# Nixie_clock.net
KiCad netlist of a schematic drawn in EAGLE
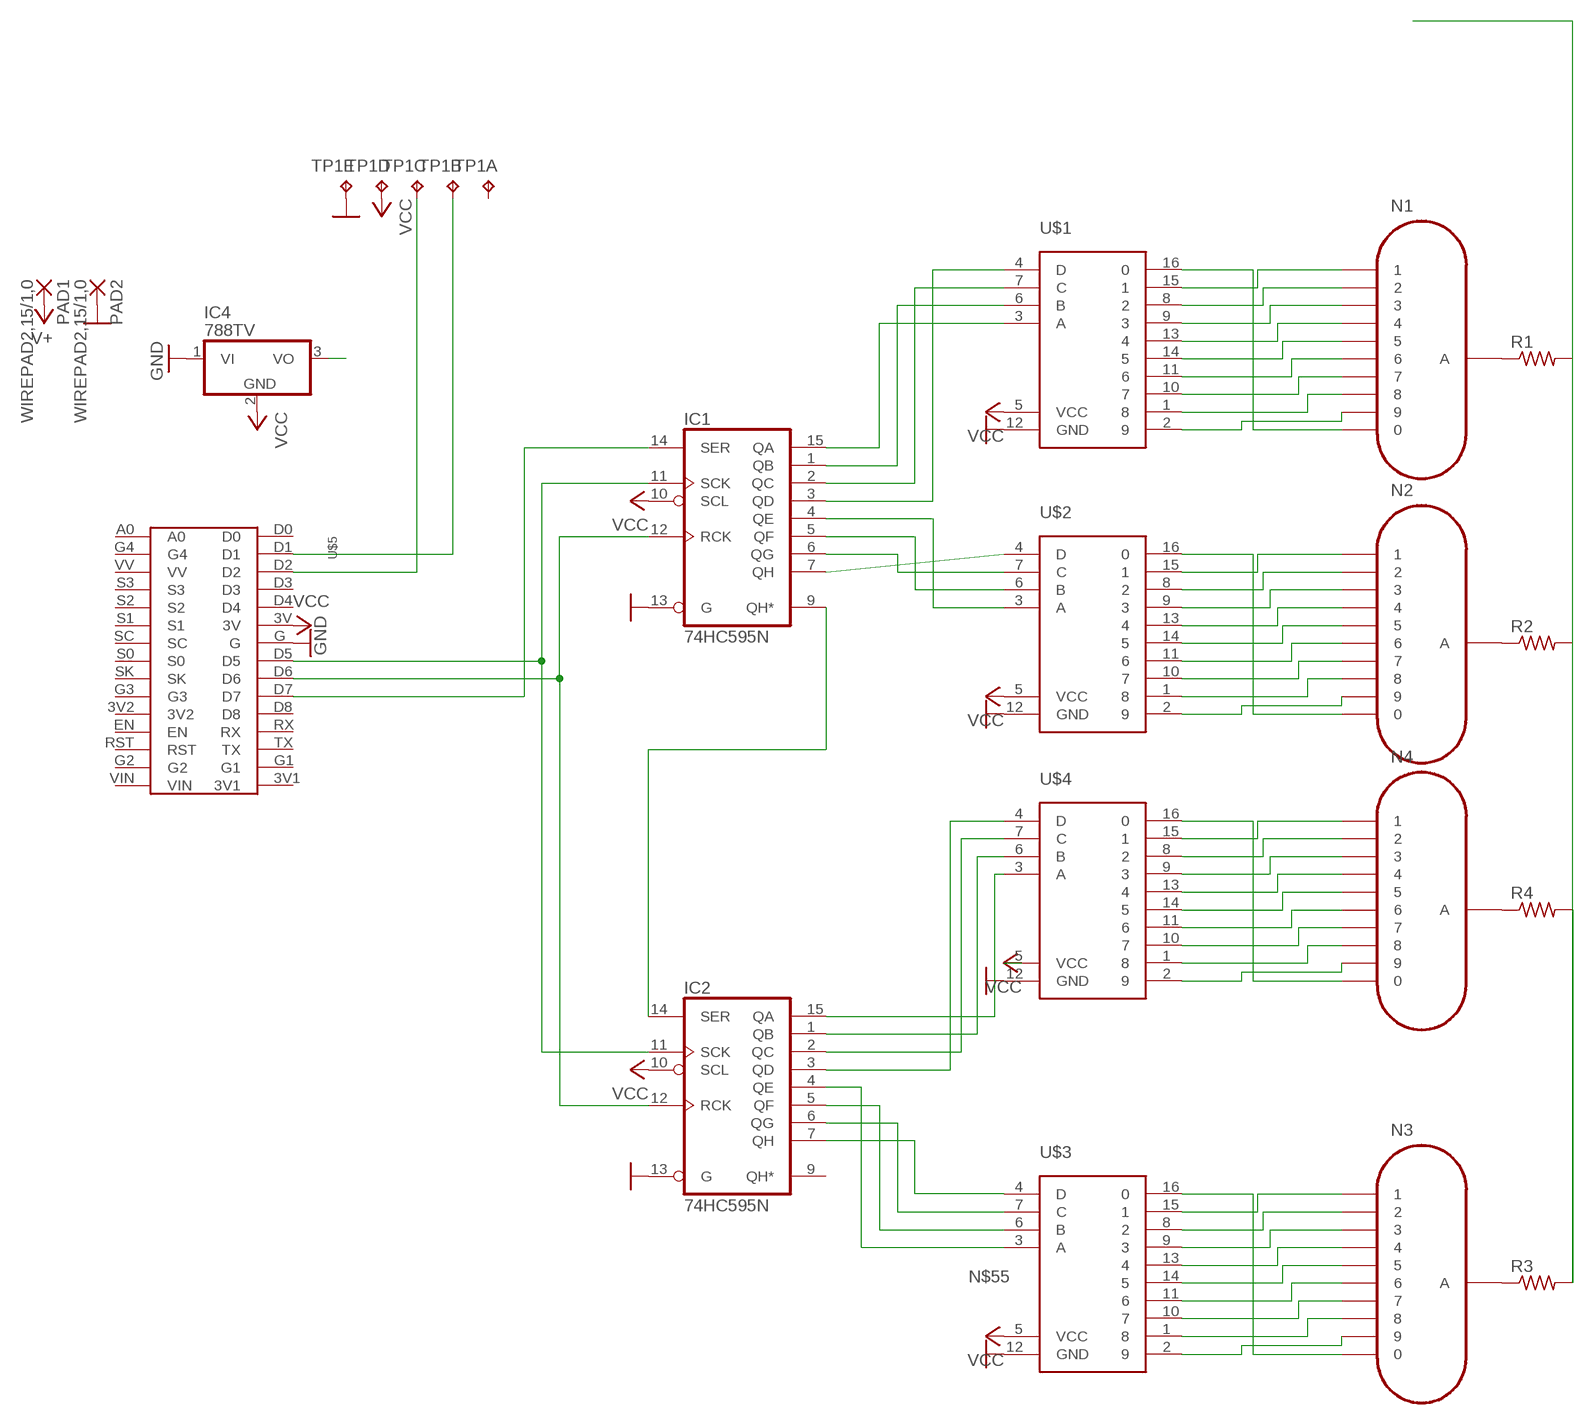
[diagram p0: schematic, sheet 1]
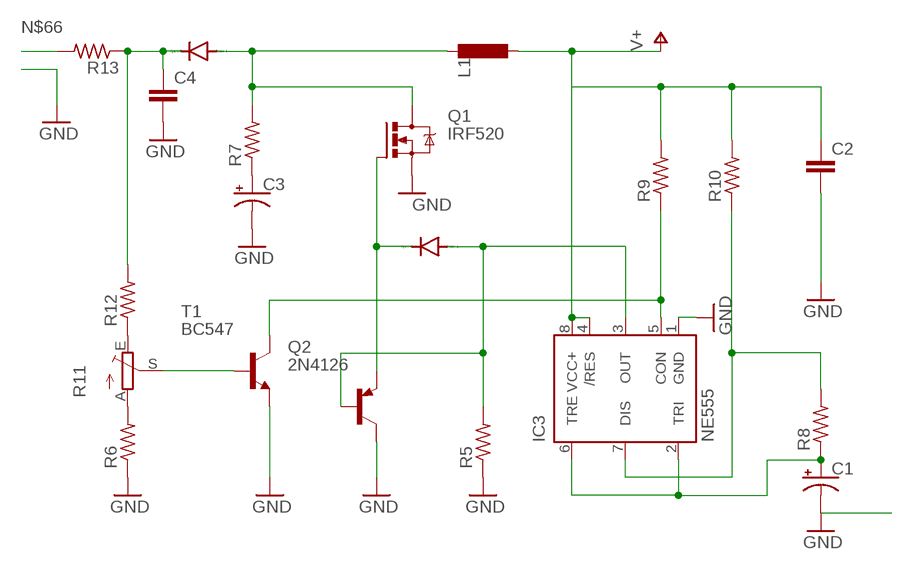
[diagram p1: schematic, sheet 2]

(export (version "E")
  (design (tool "Eeschema 10.0.6"))
  (components
    (comp (ref "C1")
      (value "CPOL-USTAP5-80")
      (footprint "eagle-import:TAP5-80")
      (libsource (lib "eagle-import") (part "CPOL-USTAP5-80"))
    )
    (comp (ref "C2")
      (value "C-EU025-025X050")
      (footprint "eagle-import:C025-025X050")
      (libsource (lib "eagle-import") (part "C-EU025-025X050"))
    )
    (comp (ref "C3")
      (value "CPOL-USTAP5-80")
      (footprint "eagle-import:TAP5-80")
      (libsource (lib "eagle-import") (part "CPOL-USTAP5-80"))
    )
    (comp (ref "C4")
      (value "C-EU025-025X050")
      (footprint "eagle-import:C025-025X050")
      (libsource (lib "eagle-import") (part "C-EU025-025X050"))
    )
    (comp (ref "D1")
      (value "1N4004")
      (footprint "eagle-import:DO41-10")
      (libsource (lib "eagle-import") (part "1N4004"))
    )
    (comp (ref "D2")
      (value "1N4004")
      (footprint "eagle-import:DO41-10")
      (libsource (lib "eagle-import") (part "1N4004"))
    )
    (comp (ref "IC3")
      (value "NE555")
      (footprint "eagle-import:DIL-08")
      (fields (field (name "MF") "Arrow Electronics") (field (name "MPN") "NE555N"))
      (libsource (lib "eagle-import") (part "NE555"))
    )
    (comp (ref "L1")
      (value "L-EU0204V")
      (footprint "eagle-import:0204V")
      (libsource (lib "eagle-import") (part "L-EU0204V"))
    )
    (comp (ref "Q1")
      (value "IRF520")
      (footprint "eagle-import:TO220BV")
      (libsource (lib "eagle-import") (part "IRF520"))
    )
    (comp (ref "Q2")
      (value "2N4126")
      (footprint "eagle-import:TO92-CBE")
      (libsource (lib "eagle-import") (part "2N4126"))
    )
    (comp (ref "R5")
      (value "R-US_0204/7")
      (footprint "eagle-import:0204_7")
      (libsource (lib "eagle-import") (part "rcl_334_R-US_0204/7"))
    )
    (comp (ref "R6")
      (value "R-US_0204/7")
      (footprint "eagle-import:0204_7")
      (libsource (lib "eagle-import") (part "rcl_334_R-US_0204/7"))
    )
    (comp (ref "R7")
      (value "R-US_0204/7")
      (footprint "eagle-import:0204_7")
      (libsource (lib "eagle-import") (part "rcl_334_R-US_0204/7"))
    )
    (comp (ref "R8")
      (value "R-US_0204/7")
      (footprint "eagle-import:0204_7")
      (libsource (lib "eagle-import") (part "rcl_334_R-US_0204/7"))
    )
    (comp (ref "R9")
      (value "R-US_0204/7")
      (footprint "eagle-import:0204_7")
      (libsource (lib "eagle-import") (part "rcl_334_R-US_0204/7"))
    )
    (comp (ref "R10")
      (value "R-US_0204/7")
      (footprint "eagle-import:0204_7")
      (libsource (lib "eagle-import") (part "rcl_334_R-US_0204/7"))
    )
    (comp (ref "R11")
      (value "TRIM_EU-S75H")
      (footprint "eagle-import:S75H")
      (libsource (lib "eagle-import") (part "TRIM_EU-S75H"))
    )
    (comp (ref "R12")
      (value "R-US_0204/7")
      (footprint "eagle-import:0204_7")
      (libsource (lib "eagle-import") (part "rcl_334_R-US_0204/7"))
    )
    (comp (ref "R13")
      (value "R-US_0204/7")
      (footprint "eagle-import:0204_7")
      (libsource (lib "eagle-import") (part "rcl_334_R-US_0204/7"))
    )
    (comp (ref "T1")
      (value "BC547")
      (footprint "eagle-import:TO92")
      (libsource (lib "eagle-import") (part "BC547"))
    )
    (comp (ref "IC1")
      (value "74HC595N")
      (footprint "eagle-import:DIL16")
      (libsource (lib "eagle-import") (part "74595NHC"))
    )
    (comp (ref "IC2")
      (value "74HC595N")
      (footprint "eagle-import:DIL16")
      (libsource (lib "eagle-import") (part "74595NHC"))
    )
    (comp (ref "IC4")
      (value "788TV")
      (footprint "eagle-import:TO220V")
      (libsource (lib "eagle-import") (part "78TV8"))
    )
    (comp (ref "N1")
      (value "IN-12A")
      (footprint "eagle-import:IN-12")
      (libsource (lib "eagle-import") (part "IN-12A"))
    )
    (comp (ref "N2")
      (value "IN-12A")
      (footprint "eagle-import:IN-12")
      (libsource (lib "eagle-import") (part "IN-12A"))
    )
    (comp (ref "N3")
      (value "IN-12A")
      (footprint "eagle-import:IN-12")
      (libsource (lib "eagle-import") (part "IN-12A"))
    )
    (comp (ref "N4")
      (value "IN-12A")
      (footprint "eagle-import:IN-12")
      (libsource (lib "eagle-import") (part "IN-12A"))
    )
    (comp (ref "PAD1")
      (value "WIREPAD2,15/1,0")
      (footprint "eagle-import:2,15_1,0")
      (libsource (lib "eagle-import") (part "WIREPAD2,15/1,0"))
    )
    (comp (ref "PAD2")
      (value "WIREPAD2,15/1,0")
      (footprint "eagle-import:2,15_1,0")
      (libsource (lib "eagle-import") (part "WIREPAD2,15/1,0"))
    )
    (comp (ref "R1")
      (value "R-US_0207/10")
      (footprint "eagle-import:0207_10")
      (libsource (lib "eagle-import") (part "R-US_0207/10"))
    )
    (comp (ref "R2")
      (value "R-US_0207/10")
      (footprint "eagle-import:0207_10")
      (libsource (lib "eagle-import") (part "R-US_0207/10"))
    )
    (comp (ref "R3")
      (value "R-US_0207/10")
      (footprint "eagle-import:0207_10")
      (libsource (lib "eagle-import") (part "R-US_0207/10"))
    )
    (comp (ref "R4")
      (value "R-US_0207/10")
      (footprint "eagle-import:0207_10")
      (libsource (lib "eagle-import") (part "R-US_0207/10"))
    )
    (comp (ref "TP1")
      (value "TP5P5-25-13")
      (footprint "eagle-import:P5-25-13")
      (libsource (lib "eagle-import") (part "TP5P5-25-13"))
    )
    (comp (ref "U$1")
      (value "K155ID1")
      (footprint "eagle-import:DIL16-KIT")
      (libsource (lib "eagle-import") (part "K155ID1"))
    )
    (comp (ref "U$2")
      (value "K155ID1")
      (footprint "eagle-import:DIL16-KIT")
      (libsource (lib "eagle-import") (part "K155ID1"))
    )
    (comp (ref "U$3")
      (value "K155ID1")
      (footprint "eagle-import:DIL16-KIT")
      (libsource (lib "eagle-import") (part "K155ID1"))
    )
    (comp (ref "U$4")
      (value "K155ID1")
      (footprint "eagle-import:DIL16-KIT")
      (libsource (lib "eagle-import") (part "K155ID1"))
    )
    (comp (ref "U$5")
      (value "LOLIN")
      (footprint "eagle-import:LOLIN")
      (libsource (lib "eagle-import") (part "LOLIN"))
    )
  )
  (nets
    (net (code "1") (name "GND") (class "Default")
      (node (ref "C1") (pin "-") (pinfunction "-_-") (pintype "passive"))
      (node (ref "C2") (pin "2") (pinfunction "2_2") (pintype "passive"))
      (node (ref "C3") (pin "-") (pinfunction "-_-") (pintype "passive"))
      (node (ref "C4") (pin "2") (pinfunction "2_2") (pintype "passive"))
      (node (ref "IC1") (pin "13") (pinfunction "G_13") (pintype "input"))
      (node (ref "IC2") (pin "13") (pinfunction "G_13") (pintype "input"))
      (node (ref "IC3") (pin "1") (pinfunction "GND_1") (pintype "power_in"))
      (node (ref "IC4") (pin "1") (pinfunction "VI_1") (pintype "input"))
      (node (ref "PAD2") (pin "1") (pinfunction "P_1") (pintype "passive"))
      (node (ref "Q1") (pin "S") (pinfunction "S_S") (pintype "passive"))
      (node (ref "Q2") (pin "C") (pinfunction "C_C") (pintype "passive"))
      (node (ref "R5") (pin "1") (pinfunction "1_1") (pintype "passive"))
      (node (ref "R6") (pin "1") (pinfunction "1_1") (pintype "passive"))
      (node (ref "T1") (pin "1") (pinfunction "E_1") (pintype "passive"))
      (node (ref "TP1") (pin "TP-5") (pinfunction "TP_TP-5") (pintype "input"))
      (node (ref "U$1") (pin "12") (pinfunction "GND_12") (pintype "bidirectional"))
      (node (ref "U$2") (pin "12") (pinfunction "GND_12") (pintype "bidirectional"))
      (node (ref "U$3") (pin "12") (pinfunction "GND_12") (pintype "bidirectional"))
      (node (ref "U$4") (pin "12") (pinfunction "GND_12") (pintype "bidirectional"))
      (node (ref "U$5") (pin "G") (pinfunction "G_G") (pintype "bidirectional"))
    )
    (net (code "2") (name "N$55") (class "Default")
      (node (ref "IC2") (pin "5") (pinfunction "QF_5") (pintype "tri_state"))
      (node (ref "U$3") (pin "6") (pinfunction "B_6") (pintype "input"))
    )
    (net (code "3") (name "N$66") (class "Default")
      (node (ref "R1") (pin "2") (pinfunction "2_2") (pintype "passive"))
      (node (ref "R13") (pin "2") (pinfunction "2_2") (pintype "passive"))
      (node (ref "R2") (pin "2") (pinfunction "2_2") (pintype "passive"))
      (node (ref "R3") (pin "2") (pinfunction "2_2") (pintype "passive"))
      (node (ref "R4") (pin "2") (pinfunction "2_2") (pintype "passive"))
    )
    (net (code "4") (name "Net-(C3-Pad+)") (class "Default")
      (node (ref "C3") (pin "+") (pinfunction "+_+") (pintype "passive"))
      (node (ref "R7") (pin "1") (pinfunction "1_1") (pintype "passive"))
    )
    (net (code "5") (name "Net-(C4-Pad1)") (class "Default")
      (node (ref "C4") (pin "1") (pinfunction "1_1") (pintype "passive"))
      (node (ref "D2") (pin "C") (pinfunction "C_C") (pintype "passive"))
      (node (ref "R12") (pin "2") (pinfunction "2_2") (pintype "passive"))
      (node (ref "R13") (pin "1") (pinfunction "1_1") (pintype "passive"))
    )
    (net (code "6") (name "Net-(D1-PadC)") (class "Default")
      (node (ref "D1") (pin "C") (pinfunction "C_C") (pintype "passive"))
      (node (ref "Q1") (pin "G") (pinfunction "G_G") (pintype "passive"))
      (node (ref "Q2") (pin "E") (pinfunction "E_E") (pintype "passive"))
    )
    (net (code "7") (name "Net-(D2-PadA)") (class "Default")
      (node (ref "D2") (pin "A") (pinfunction "A_A") (pintype "passive"))
      (node (ref "L1") (pin "1") (pinfunction "1_1") (pintype "passive"))
      (node (ref "Q1") (pin "D") (pinfunction "D_D") (pintype "passive"))
      (node (ref "R7") (pin "2") (pinfunction "2_2") (pintype "passive"))
    )
    (net (code "8") (name "Net-(IC1A-QA)") (class "Default")
      (node (ref "IC1") (pin "15") (pinfunction "QA_15") (pintype "tri_state"))
      (node (ref "U$1") (pin "3") (pinfunction "A_3") (pintype "input"))
    )
    (net (code "9") (name "Net-(IC1A-QB)") (class "Default")
      (node (ref "IC1") (pin "1") (pinfunction "QB_1") (pintype "tri_state"))
      (node (ref "U$1") (pin "6") (pinfunction "B_6") (pintype "input"))
    )
    (net (code "10") (name "Net-(IC1A-QC)") (class "Default")
      (node (ref "IC1") (pin "2") (pinfunction "QC_2") (pintype "tri_state"))
      (node (ref "U$1") (pin "7") (pinfunction "C_7") (pintype "input"))
    )
    (net (code "11") (name "Net-(IC1A-QD)") (class "Default")
      (node (ref "IC1") (pin "3") (pinfunction "QD_3") (pintype "tri_state"))
      (node (ref "U$1") (pin "4") (pinfunction "D_4") (pintype "input"))
    )
    (net (code "12") (name "Net-(IC1A-QE)") (class "Default")
      (node (ref "IC1") (pin "4") (pinfunction "QE_4") (pintype "tri_state"))
      (node (ref "U$2") (pin "3") (pinfunction "A_3") (pintype "input"))
    )
    (net (code "13") (name "Net-(IC1A-QF)") (class "Default")
      (node (ref "IC1") (pin "5") (pinfunction "QF_5") (pintype "tri_state"))
      (node (ref "U$2") (pin "6") (pinfunction "B_6") (pintype "input"))
    )
    (net (code "14") (name "Net-(IC1A-QG)") (class "Default")
      (node (ref "IC1") (pin "6") (pinfunction "QG_6") (pintype "tri_state"))
      (node (ref "U$2") (pin "7") (pinfunction "C_7") (pintype "input"))
    )
    (net (code "15") (name "Net-(IC1A-QH)") (class "Default")
      (node (ref "IC1") (pin "7") (pinfunction "QH_7") (pintype "tri_state"))
      (node (ref "U$2") (pin "4") (pinfunction "D_4") (pintype "input"))
    )
    (net (code "16") (name "Net-(IC1A-QH*)") (class "Default")
      (node (ref "IC1") (pin "9") (pinfunction "QH*_9") (pintype "tri_state"))
      (node (ref "IC2") (pin "14") (pinfunction "SER_14") (pintype "input"))
    )
    (net (code "17") (name "Net-(IC1A-RCK)") (class "Default")
      (node (ref "IC1") (pin "12") (pinfunction "RCK_12") (pintype "input"))
      (node (ref "IC2") (pin "12") (pinfunction "RCK_12") (pintype "input"))
      (node (ref "U$5") (pin "D6") (pinfunction "D6_D6") (pintype "bidirectional"))
    )
    (net (code "18") (name "Net-(IC1A-SCK)") (class "Default")
      (node (ref "IC1") (pin "11") (pinfunction "SCK_11") (pintype "input"))
      (node (ref "IC2") (pin "11") (pinfunction "SCK_11") (pintype "input"))
      (node (ref "U$5") (pin "D5") (pinfunction "D5_D5") (pintype "bidirectional"))
    )
    (net (code "19") (name "Net-(IC1A-SER)") (class "Default")
      (node (ref "IC1") (pin "14") (pinfunction "SER_14") (pintype "input"))
      (node (ref "U$5") (pin "D7") (pinfunction "D7_D7") (pintype "bidirectional"))
    )
    (net (code "20") (name "Net-(IC2A-QA)") (class "Default")
      (node (ref "IC2") (pin "15") (pinfunction "QA_15") (pintype "tri_state"))
      (node (ref "U$4") (pin "3") (pinfunction "A_3") (pintype "input"))
    )
    (net (code "21") (name "Net-(IC2A-QB)") (class "Default")
      (node (ref "IC2") (pin "1") (pinfunction "QB_1") (pintype "tri_state"))
      (node (ref "U$4") (pin "6") (pinfunction "B_6") (pintype "input"))
    )
    (net (code "22") (name "Net-(IC2A-QC)") (class "Default")
      (node (ref "IC2") (pin "2") (pinfunction "QC_2") (pintype "tri_state"))
      (node (ref "U$4") (pin "7") (pinfunction "C_7") (pintype "input"))
    )
    (net (code "23") (name "Net-(IC2A-QD)") (class "Default")
      (node (ref "IC2") (pin "3") (pinfunction "QD_3") (pintype "tri_state"))
      (node (ref "U$4") (pin "4") (pinfunction "D_4") (pintype "input"))
    )
    (net (code "24") (name "Net-(IC2A-QE)") (class "Default")
      (node (ref "IC2") (pin "4") (pinfunction "QE_4") (pintype "tri_state"))
      (node (ref "U$3") (pin "3") (pinfunction "A_3") (pintype "input"))
    )
    (net (code "25") (name "Net-(IC2A-QG)") (class "Default")
      (node (ref "IC2") (pin "6") (pinfunction "QG_6") (pintype "tri_state"))
      (node (ref "U$3") (pin "7") (pinfunction "C_7") (pintype "input"))
    )
    (net (code "26") (name "Net-(IC2A-QH)") (class "Default")
      (node (ref "IC2") (pin "7") (pinfunction "QH_7") (pintype "tri_state"))
      (node (ref "U$3") (pin "4") (pinfunction "D_4") (pintype "input"))
    )
    (net (code "27") (name "Net-(IC3-CON)") (class "Default")
      (node (ref "IC3") (pin "5") (pinfunction "CON_5") (pintype "input"))
      (node (ref "R9") (pin "1") (pinfunction "1_1") (pintype "passive"))
      (node (ref "T1") (pin "3") (pinfunction "C_3") (pintype "passive"))
    )
    (net (code "28") (name "Net-(IC3-DIS)") (class "Default")
      (node (ref "IC3") (pin "7") (pinfunction "DIS_7") (pintype "input"))
      (node (ref "R10") (pin "1") (pinfunction "1_1") (pintype "passive"))
      (node (ref "R8") (pin "2") (pinfunction "2_2") (pintype "passive"))
    )
    (net (code "29") (name "Net-(IC3-OUT)") (class "Default")
      (node (ref "D1") (pin "A") (pinfunction "A_A") (pintype "passive"))
      (node (ref "IC3") (pin "3") (pinfunction "OUT_3") (pintype "output"))
      (node (ref "Q2") (pin "B") (pinfunction "B_B") (pintype "passive"))
      (node (ref "R5") (pin "2") (pinfunction "2_2") (pintype "passive"))
    )
    (net (code "30") (name "Net-(IC3-TRE)") (class "Default")
      (node (ref "C1") (pin "+") (pinfunction "+_+") (pintype "passive"))
      (node (ref "IC3") (pin "2") (pinfunction "TRI_2") (pintype "input"))
      (node (ref "IC3") (pin "6") (pinfunction "TRE_6") (pintype "input"))
      (node (ref "R8") (pin "1") (pinfunction "1_1") (pintype "passive"))
    )
    (net (code "31") (name "Net-(N1-PadA)") (class "Default")
      (node (ref "N1") (pin "A") (pinfunction "A_A") (pintype "bidirectional"))
      (node (ref "R1") (pin "1") (pinfunction "1_1") (pintype "passive"))
    )
    (net (code "32") (name "Net-(N2-PadA)") (class "Default")
      (node (ref "N2") (pin "A") (pinfunction "A_A") (pintype "bidirectional"))
      (node (ref "R2") (pin "1") (pinfunction "1_1") (pintype "passive"))
    )
    (net (code "33") (name "Net-(N3-PadA)") (class "Default")
      (node (ref "N3") (pin "A") (pinfunction "A_A") (pintype "bidirectional"))
      (node (ref "R3") (pin "1") (pinfunction "1_1") (pintype "passive"))
    )
    (net (code "34") (name "Net-(N4-PadA)") (class "Default")
      (node (ref "N4") (pin "A") (pinfunction "A_A") (pintype "bidirectional"))
      (node (ref "R4") (pin "1") (pinfunction "1_1") (pintype "passive"))
    )
    (net (code "35") (name "Net-(R11-PadA)") (class "Default")
      (node (ref "R11") (pin "A") (pinfunction "A_A") (pintype "passive"))
      (node (ref "R6") (pin "2") (pinfunction "2_2") (pintype "passive"))
    )
    (net (code "36") (name "Net-(R11-PadE)") (class "Default")
      (node (ref "R11") (pin "E") (pinfunction "E_E") (pintype "passive"))
      (node (ref "R12") (pin "1") (pinfunction "1_1") (pintype "passive"))
    )
    (net (code "37") (name "Net-(T1-B)") (class "Default")
      (node (ref "R11") (pin "S") (pinfunction "S_S") (pintype "passive"))
      (node (ref "T1") (pin "2") (pinfunction "B_2") (pintype "passive"))
    )
    (net (code "38") (name "Net-(TP1B-TP)") (class "Default")
      (node (ref "TP1") (pin "TP-2") (pinfunction "TP_TP-2") (pintype "input"))
      (node (ref "U$5") (pin "D1") (pinfunction "D1_D1") (pintype "bidirectional"))
    )
    (net (code "39") (name "Net-(TP1C-TP)") (class "Default")
      (node (ref "TP1") (pin "TP-3") (pinfunction "TP_TP-3") (pintype "input"))
      (node (ref "U$5") (pin "D2") (pinfunction "D2_D2") (pintype "bidirectional"))
    )
    (net (code "40") (name "Net-(U$1-0)") (class "Default")
      (node (ref "N1") (pin "0") (pinfunction "0_0") (pintype "bidirectional"))
      (node (ref "U$1") (pin "16") (pinfunction "0_16") (pintype "bidirectional"))
    )
    (net (code "41") (name "Net-(U$1-1)") (class "Default")
      (node (ref "N1") (pin "1") (pinfunction "1_1") (pintype "bidirectional"))
      (node (ref "U$1") (pin "15") (pinfunction "1_15") (pintype "bidirectional"))
    )
    (net (code "42") (name "Net-(U$1-2)") (class "Default")
      (node (ref "N1") (pin "2") (pinfunction "2_2") (pintype "bidirectional"))
      (node (ref "U$1") (pin "8") (pinfunction "2_8") (pintype "bidirectional"))
    )
    (net (code "43") (name "Net-(U$1-3)") (class "Default")
      (node (ref "N1") (pin "3") (pinfunction "3_3") (pintype "bidirectional"))
      (node (ref "U$1") (pin "9") (pinfunction "3_9") (pintype "bidirectional"))
    )
    (net (code "44") (name "Net-(U$1-4)") (class "Default")
      (node (ref "N1") (pin "4") (pinfunction "4_4") (pintype "bidirectional"))
      (node (ref "U$1") (pin "13") (pinfunction "4_13") (pintype "bidirectional"))
    )
    (net (code "45") (name "Net-(U$1-5)") (class "Default")
      (node (ref "N1") (pin "5") (pinfunction "5_5") (pintype "bidirectional"))
      (node (ref "U$1") (pin "14") (pinfunction "5_14") (pintype "bidirectional"))
    )
    (net (code "46") (name "Net-(U$1-6)") (class "Default")
      (node (ref "N1") (pin "6") (pinfunction "6_6") (pintype "bidirectional"))
      (node (ref "U$1") (pin "11") (pinfunction "6_11") (pintype "bidirectional"))
    )
    (net (code "47") (name "Net-(U$1-7)") (class "Default")
      (node (ref "N1") (pin "7") (pinfunction "7_7") (pintype "bidirectional"))
      (node (ref "U$1") (pin "10") (pinfunction "7_10") (pintype "bidirectional"))
    )
    (net (code "48") (name "Net-(U$1-8)") (class "Default")
      (node (ref "N1") (pin "8") (pinfunction "8_8") (pintype "bidirectional"))
      (node (ref "U$1") (pin "1") (pinfunction "8_1") (pintype "bidirectional"))
    )
    (net (code "49") (name "Net-(U$1-9)") (class "Default")
      (node (ref "N1") (pin "9") (pinfunction "9_9") (pintype "bidirectional"))
      (node (ref "U$1") (pin "2") (pinfunction "9_2") (pintype "bidirectional"))
    )
    (net (code "50") (name "Net-(U$2-0)") (class "Default")
      (node (ref "N2") (pin "0") (pinfunction "0_0") (pintype "bidirectional"))
      (node (ref "U$2") (pin "16") (pinfunction "0_16") (pintype "bidirectional"))
    )
    (net (code "51") (name "Net-(U$2-1)") (class "Default")
      (node (ref "N2") (pin "1") (pinfunction "1_1") (pintype "bidirectional"))
      (node (ref "U$2") (pin "15") (pinfunction "1_15") (pintype "bidirectional"))
    )
    (net (code "52") (name "Net-(U$2-2)") (class "Default")
      (node (ref "N2") (pin "2") (pinfunction "2_2") (pintype "bidirectional"))
      (node (ref "U$2") (pin "8") (pinfunction "2_8") (pintype "bidirectional"))
    )
    (net (code "53") (name "Net-(U$2-3)") (class "Default")
      (node (ref "N2") (pin "3") (pinfunction "3_3") (pintype "bidirectional"))
      (node (ref "U$2") (pin "9") (pinfunction "3_9") (pintype "bidirectional"))
    )
    (net (code "54") (name "Net-(U$2-4)") (class "Default")
      (node (ref "N2") (pin "4") (pinfunction "4_4") (pintype "bidirectional"))
      (node (ref "U$2") (pin "13") (pinfunction "4_13") (pintype "bidirectional"))
    )
    (net (code "55") (name "Net-(U$2-5)") (class "Default")
      (node (ref "N2") (pin "5") (pinfunction "5_5") (pintype "bidirectional"))
      (node (ref "U$2") (pin "14") (pinfunction "5_14") (pintype "bidirectional"))
    )
    (net (code "56") (name "Net-(U$2-6)") (class "Default")
      (node (ref "N2") (pin "6") (pinfunction "6_6") (pintype "bidirectional"))
      (node (ref "U$2") (pin "11") (pinfunction "6_11") (pintype "bidirectional"))
    )
    (net (code "57") (name "Net-(U$2-7)") (class "Default")
      (node (ref "N2") (pin "7") (pinfunction "7_7") (pintype "bidirectional"))
      (node (ref "U$2") (pin "10") (pinfunction "7_10") (pintype "bidirectional"))
    )
    (net (code "58") (name "Net-(U$2-8)") (class "Default")
      (node (ref "N2") (pin "8") (pinfunction "8_8") (pintype "bidirectional"))
      (node (ref "U$2") (pin "1") (pinfunction "8_1") (pintype "bidirectional"))
    )
    (net (code "59") (name "Net-(U$2-9)") (class "Default")
      (node (ref "N2") (pin "9") (pinfunction "9_9") (pintype "bidirectional"))
      (node (ref "U$2") (pin "2") (pinfunction "9_2") (pintype "bidirectional"))
    )
    (net (code "60") (name "Net-(U$3-0)") (class "Default")
      (node (ref "N3") (pin "0") (pinfunction "0_0") (pintype "bidirectional"))
      (node (ref "U$3") (pin "16") (pinfunction "0_16") (pintype "bidirectional"))
    )
    (net (code "61") (name "Net-(U$3-1)") (class "Default")
      (node (ref "N3") (pin "1") (pinfunction "1_1") (pintype "bidirectional"))
      (node (ref "U$3") (pin "15") (pinfunction "1_15") (pintype "bidirectional"))
    )
    (net (code "62") (name "Net-(U$3-2)") (class "Default")
      (node (ref "N3") (pin "2") (pinfunction "2_2") (pintype "bidirectional"))
      (node (ref "U$3") (pin "8") (pinfunction "2_8") (pintype "bidirectional"))
    )
    (net (code "63") (name "Net-(U$3-3)") (class "Default")
      (node (ref "N3") (pin "3") (pinfunction "3_3") (pintype "bidirectional"))
      (node (ref "U$3") (pin "9") (pinfunction "3_9") (pintype "bidirectional"))
    )
    (net (code "64") (name "Net-(U$3-4)") (class "Default")
      (node (ref "N3") (pin "4") (pinfunction "4_4") (pintype "bidirectional"))
      (node (ref "U$3") (pin "13") (pinfunction "4_13") (pintype "bidirectional"))
    )
    (net (code "65") (name "Net-(U$3-5)") (class "Default")
      (node (ref "N3") (pin "5") (pinfunction "5_5") (pintype "bidirectional"))
      (node (ref "U$3") (pin "14") (pinfunction "5_14") (pintype "bidirectional"))
    )
    (net (code "66") (name "Net-(U$3-6)") (class "Default")
      (node (ref "N3") (pin "6") (pinfunction "6_6") (pintype "bidirectional"))
      (node (ref "U$3") (pin "11") (pinfunction "6_11") (pintype "bidirectional"))
    )
    (net (code "67") (name "Net-(U$3-7)") (class "Default")
      (node (ref "N3") (pin "7") (pinfunction "7_7") (pintype "bidirectional"))
      (node (ref "U$3") (pin "10") (pinfunction "7_10") (pintype "bidirectional"))
    )
    (net (code "68") (name "Net-(U$3-8)") (class "Default")
      (node (ref "N3") (pin "8") (pinfunction "8_8") (pintype "bidirectional"))
      (node (ref "U$3") (pin "1") (pinfunction "8_1") (pintype "bidirectional"))
    )
    (net (code "69") (name "Net-(U$3-9)") (class "Default")
      (node (ref "N3") (pin "9") (pinfunction "9_9") (pintype "bidirectional"))
      (node (ref "U$3") (pin "2") (pinfunction "9_2") (pintype "bidirectional"))
    )
    (net (code "70") (name "Net-(U$4-0)") (class "Default")
      (node (ref "N4") (pin "0") (pinfunction "0_0") (pintype "bidirectional"))
      (node (ref "U$4") (pin "16") (pinfunction "0_16") (pintype "bidirectional"))
    )
    (net (code "71") (name "Net-(U$4-1)") (class "Default")
      (node (ref "N4") (pin "1") (pinfunction "1_1") (pintype "bidirectional"))
      (node (ref "U$4") (pin "15") (pinfunction "1_15") (pintype "bidirectional"))
    )
    (net (code "72") (name "Net-(U$4-2)") (class "Default")
      (node (ref "N4") (pin "2") (pinfunction "2_2") (pintype "bidirectional"))
      (node (ref "U$4") (pin "8") (pinfunction "2_8") (pintype "bidirectional"))
    )
    (net (code "73") (name "Net-(U$4-3)") (class "Default")
      (node (ref "N4") (pin "3") (pinfunction "3_3") (pintype "bidirectional"))
      (node (ref "U$4") (pin "9") (pinfunction "3_9") (pintype "bidirectional"))
    )
    (net (code "74") (name "Net-(U$4-4)") (class "Default")
      (node (ref "N4") (pin "4") (pinfunction "4_4") (pintype "bidirectional"))
      (node (ref "U$4") (pin "13") (pinfunction "4_13") (pintype "bidirectional"))
    )
    (net (code "75") (name "Net-(U$4-5)") (class "Default")
      (node (ref "N4") (pin "5") (pinfunction "5_5") (pintype "bidirectional"))
      (node (ref "U$4") (pin "14") (pinfunction "5_14") (pintype "bidirectional"))
    )
    (net (code "76") (name "Net-(U$4-6)") (class "Default")
      (node (ref "N4") (pin "6") (pinfunction "6_6") (pintype "bidirectional"))
      (node (ref "U$4") (pin "11") (pinfunction "6_11") (pintype "bidirectional"))
    )
    (net (code "77") (name "Net-(U$4-7)") (class "Default")
      (node (ref "N4") (pin "7") (pinfunction "7_7") (pintype "bidirectional"))
      (node (ref "U$4") (pin "10") (pinfunction "7_10") (pintype "bidirectional"))
    )
    (net (code "78") (name "Net-(U$4-8)") (class "Default")
      (node (ref "N4") (pin "8") (pinfunction "8_8") (pintype "bidirectional"))
      (node (ref "U$4") (pin "1") (pinfunction "8_1") (pintype "bidirectional"))
    )
    (net (code "79") (name "Net-(U$4-9)") (class "Default")
      (node (ref "N4") (pin "9") (pinfunction "9_9") (pintype "bidirectional"))
      (node (ref "U$4") (pin "2") (pinfunction "9_2") (pintype "bidirectional"))
    )
    (net (code "80") (name "V+") (class "Default")
      (node (ref "C2") (pin "1") (pinfunction "1_1") (pintype "passive"))
      (node (ref "IC3") (pin "4") (pinfunction "/RES_4") (pintype "input"))
      (node (ref "IC3") (pin "8") (pinfunction "VCC+_8") (pintype "power_in"))
      (node (ref "IC4") (pin "3") (pinfunction "VO_3") (pintype "passive"))
      (node (ref "L1") (pin "2") (pinfunction "2_2") (pintype "passive"))
      (node (ref "PAD1") (pin "1") (pinfunction "P_1") (pintype "passive"))
      (node (ref "R10") (pin "2") (pinfunction "2_2") (pintype "passive"))
      (node (ref "R9") (pin "2") (pinfunction "2_2") (pintype "passive"))
    )
    (net (code "81") (name "VCC") (class "Default")
      (node (ref "IC1") (pin "10") (pinfunction "SCL_10") (pintype "input"))
      (node (ref "IC2") (pin "10") (pinfunction "SCL_10") (pintype "input"))
      (node (ref "IC4") (pin "2") (pinfunction "GND_2") (pintype "passive"))
      (node (ref "TP1") (pin "TP-4") (pinfunction "TP_TP-4") (pintype "input"))
      (node (ref "U$1") (pin "5") (pinfunction "VCC_5") (pintype "bidirectional"))
      (node (ref "U$2") (pin "5") (pinfunction "VCC_5") (pintype "bidirectional"))
      (node (ref "U$3") (pin "5") (pinfunction "VCC_5") (pintype "bidirectional"))
      (node (ref "U$4") (pin "5") (pinfunction "VCC_5") (pintype "bidirectional"))
      (node (ref "U$5") (pin "3V") (pinfunction "3V_3V") (pintype "bidirectional"))
    )
    (net (code "82") (name "unconnected-(IC2A-QH*-Pad9)") (class "Default")
      (node (ref "IC2") (pin "9") (pinfunction "QH*_9") (pintype "tri_state"))
    )
    (net (code "83") (name "unconnected-(TP1A-TP-PadTP-1)") (class "Default")
      (node (ref "TP1") (pin "TP-1") (pinfunction "TP_TP-1") (pintype "input"))
    )
    (net (code "84") (name "unconnected-(U$5-Pad3V1)") (class "Default")
      (node (ref "U$5") (pin "3V1") (pinfunction "3V1_3V1") (pintype "bidirectional"))
    )
    (net (code "85") (name "unconnected-(U$5-Pad3V2)") (class "Default")
      (node (ref "U$5") (pin "3V2") (pinfunction "3V2_3V2") (pintype "bidirectional"))
    )
    (net (code "86") (name "unconnected-(U$5-PadA0)") (class "Default")
      (node (ref "U$5") (pin "A0") (pinfunction "A0_A0") (pintype "bidirectional"))
    )
    (net (code "87") (name "unconnected-(U$5-PadD0)") (class "Default")
      (node (ref "U$5") (pin "D0") (pinfunction "D0_D0") (pintype "bidirectional"))
    )
    (net (code "88") (name "unconnected-(U$5-PadD3)") (class "Default")
      (node (ref "U$5") (pin "D3") (pinfunction "D3_D3") (pintype "bidirectional"))
    )
    (net (code "89") (name "unconnected-(U$5-PadD4)") (class "Default")
      (node (ref "U$5") (pin "D4") (pinfunction "D4_D4") (pintype "bidirectional"))
    )
    (net (code "90") (name "unconnected-(U$5-PadD8)") (class "Default")
      (node (ref "U$5") (pin "D8") (pinfunction "D8_D8") (pintype "bidirectional"))
    )
    (net (code "91") (name "unconnected-(U$5-PadEN)") (class "Default")
      (node (ref "U$5") (pin "EN") (pinfunction "EN_EN") (pintype "bidirectional"))
    )
    (net (code "92") (name "unconnected-(U$5-PadG1)") (class "Default")
      (node (ref "U$5") (pin "G1") (pinfunction "G1_G1") (pintype "bidirectional"))
    )
    (net (code "93") (name "unconnected-(U$5-PadG2)") (class "Default")
      (node (ref "U$5") (pin "G2") (pinfunction "G2_G2") (pintype "bidirectional"))
    )
    (net (code "94") (name "unconnected-(U$5-PadG3)") (class "Default")
      (node (ref "U$5") (pin "G3") (pinfunction "G3_G3") (pintype "bidirectional"))
    )
    (net (code "95") (name "unconnected-(U$5-PadG4)") (class "Default")
      (node (ref "U$5") (pin "G4") (pinfunction "G4_G4") (pintype "bidirectional"))
    )
    (net (code "96") (name "unconnected-(U$5-PadRST)") (class "Default")
      (node (ref "U$5") (pin "RST") (pinfunction "RST_RST") (pintype "bidirectional"))
    )
    (net (code "97") (name "unconnected-(U$5-PadRX)") (class "Default")
      (node (ref "U$5") (pin "RX") (pinfunction "RX_RX") (pintype "bidirectional"))
    )
    (net (code "98") (name "unconnected-(U$5-PadS0)") (class "Default")
      (node (ref "U$5") (pin "S0") (pinfunction "S0_S0") (pintype "bidirectional"))
    )
    (net (code "99") (name "unconnected-(U$5-PadS1)") (class "Default")
      (node (ref "U$5") (pin "S1") (pinfunction "S1_S1") (pintype "bidirectional"))
    )
    (net (code "100") (name "unconnected-(U$5-PadS2)") (class "Default")
      (node (ref "U$5") (pin "S2") (pinfunction "S2_S2") (pintype "bidirectional"))
    )
    (net (code "101") (name "unconnected-(U$5-PadS3)") (class "Default")
      (node (ref "U$5") (pin "S3") (pinfunction "S3_S3") (pintype "bidirectional"))
    )
    (net (code "102") (name "unconnected-(U$5-PadSC)") (class "Default")
      (node (ref "U$5") (pin "SC") (pinfunction "SC_SC") (pintype "bidirectional"))
    )
    (net (code "103") (name "unconnected-(U$5-PadSK)") (class "Default")
      (node (ref "U$5") (pin "SK") (pinfunction "SK_SK") (pintype "bidirectional"))
    )
    (net (code "104") (name "unconnected-(U$5-PadTX)") (class "Default")
      (node (ref "U$5") (pin "TX") (pinfunction "TX_TX") (pintype "bidirectional"))
    )
    (net (code "105") (name "unconnected-(U$5-PadVIN)") (class "Default")
      (node (ref "U$5") (pin "VIN") (pinfunction "VIN_VIN") (pintype "bidirectional"))
    )
    (net (code "106") (name "unconnected-(U$5-PadVV)") (class "Default")
      (node (ref "U$5") (pin "VV") (pinfunction "VV_VV") (pintype "bidirectional"))
    )
  )
)
